# HSens.net
KiCad netlist of a schematic drawn in Altium Designer
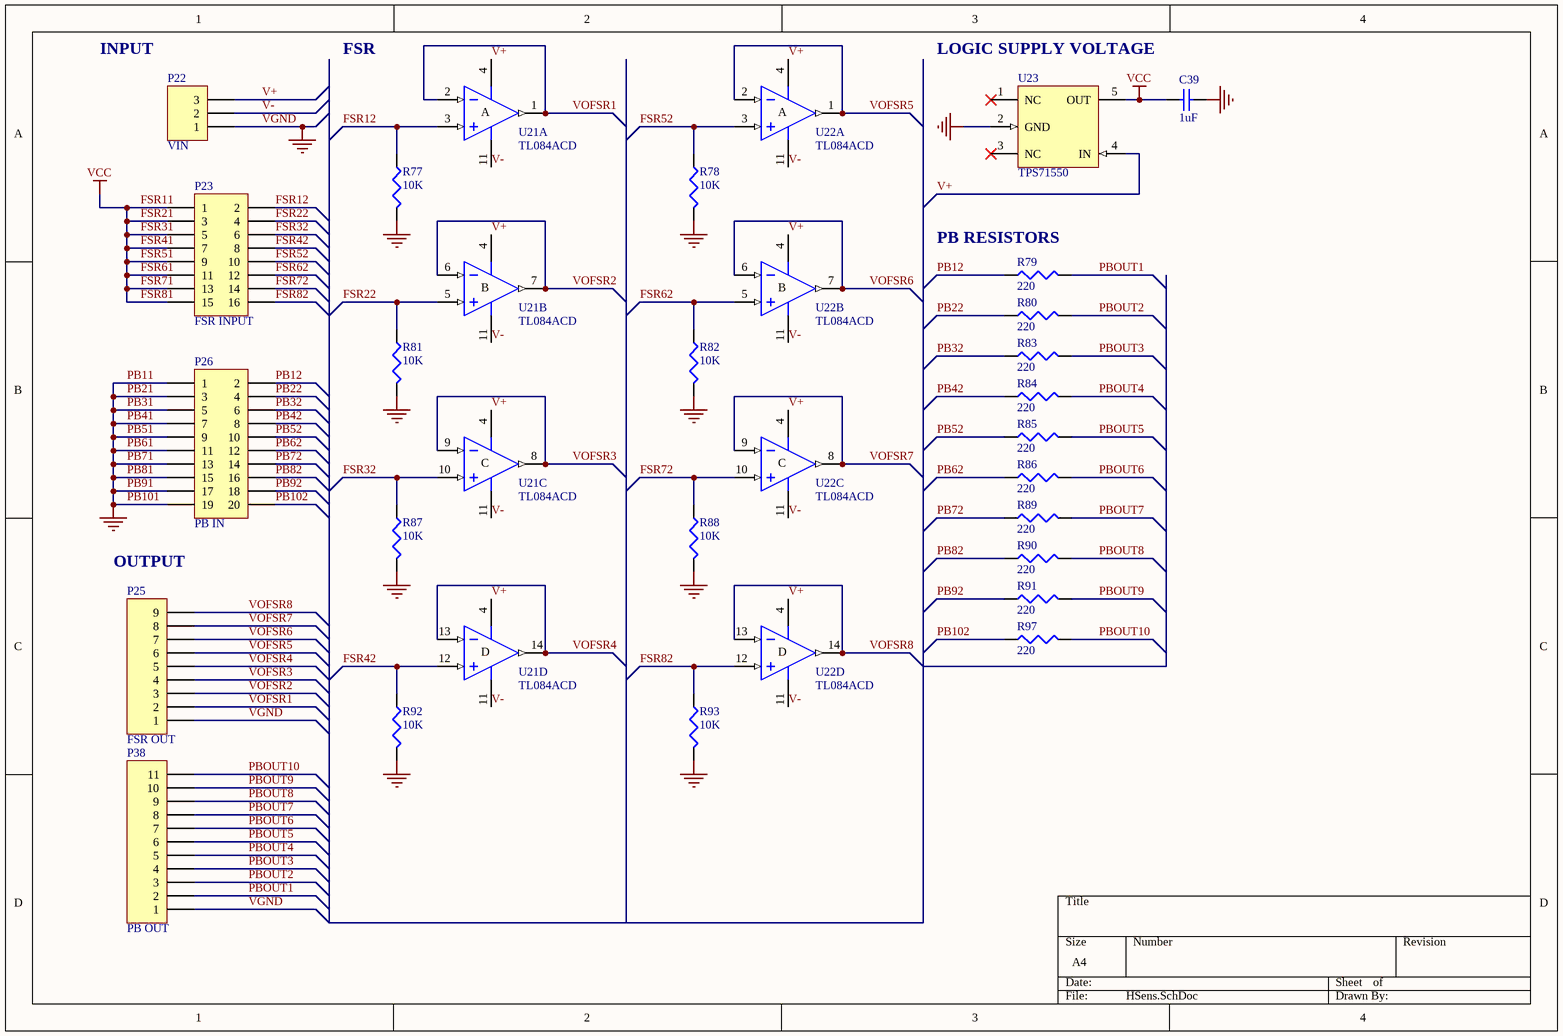
[diagram p0: HSens.SchDoc]

(export (version "E")
  (design (tool "Eeschema 10.0.6"))
  (components
    (comp (ref "C39")
      (value "1uF")
      (footprint "CAPC2012M")
      (description "Capacitor (Semiconductor SIM Model)")
      (fields (field (name "Comment") "Cap Semi") (field (name "PUBLISHER") "Altium Limited"))
      (libsource (lib "Miscellaneous Devices") (part "Cap Semi"))
    )
    (comp (ref "P22")
      (value "VIN")
      (footprint "AZUL5-3")
      (description "Header, 3-Pin")
      (fields (field (name "PUBLISHER") "Altium Limited"))
      (libsource (lib "Miscellaneous Connectors") (part "Header 3"))
    )
    (comp (ref "P23")
      (value "FSR INPUT")
      (footprint "HDR2X8")
      (description "Header, 8-Pin, Dual row")
      (fields (field (name "PUBLISHER") "Altium Limited"))
      (libsource (lib "Miscellaneous Connectors") (part "Header 8X2"))
    )
    (comp (ref "P25")
      (value "FSR OUT")
      (footprint "HDR1X9H")
      (description "Header, 9-Pin, Right Angle")
      (fields (field (name "PUBLISHER") "Altium Limited"))
      (libsource (lib "Miscellaneous Connectors") (part "Header 9H"))
    )
    (comp (ref "P26")
      (value "PB IN")
      (footprint "HDR2X10")
      (description "Header, 10-Pin, Dual row")
      (fields (field (name "PUBLISHER") "Altium Limited"))
      (libsource (lib "Miscellaneous Connectors") (part "Header 10X2"))
    )
    (comp (ref "P38")
      (value "PB OUT")
      (footprint "HDR1X11H")
      (description "Header, 11-Pin, Right Angle")
      (fields (field (name "PUBLISHER") "Altium Limited"))
      (libsource (lib "Miscellaneous Connectors") (part "Header 11H"))
    )
    (comp (ref "R77")
      (value "10K")
      (footprint "RESC3225M")
      (description "Resistor")
      (fields (field (name "Comment") "Res3") (field (name "PUBLISHER") "Altium Limited"))
      (libsource (lib "Miscellaneous Devices") (part "Res3"))
    )
    (comp (ref "R78")
      (value "10K")
      (footprint "RESC3225M")
      (description "Resistor")
      (fields (field (name "Comment") "Res3") (field (name "PUBLISHER") "Altium Limited"))
      (libsource (lib "Miscellaneous Devices") (part "Res3"))
    )
    (comp (ref "R79")
      (value "220")
      (footprint "RESC3225M")
      (description "Resistor")
      (fields (field (name "Comment") "Res3") (field (name "PUBLISHER") "Altium Limited"))
      (libsource (lib "Miscellaneous Devices") (part "Res3"))
    )
    (comp (ref "R80")
      (value "220")
      (footprint "RESC3225M")
      (description "Resistor")
      (fields (field (name "Comment") "Res3") (field (name "PUBLISHER") "Altium Limited"))
      (libsource (lib "Miscellaneous Devices") (part "Res3"))
    )
    (comp (ref "R81")
      (value "10K")
      (footprint "RESC3225M")
      (description "Resistor")
      (fields (field (name "Comment") "Res3") (field (name "PUBLISHER") "Altium Limited"))
      (libsource (lib "Miscellaneous Devices") (part "Res3"))
    )
    (comp (ref "R82")
      (value "10K")
      (footprint "RESC3225M")
      (description "Resistor")
      (fields (field (name "Comment") "Res3") (field (name "PUBLISHER") "Altium Limited"))
      (libsource (lib "Miscellaneous Devices") (part "Res3"))
    )
    (comp (ref "R83")
      (value "220")
      (footprint "RESC3225M")
      (description "Resistor")
      (fields (field (name "Comment") "Res3") (field (name "PUBLISHER") "Altium Limited"))
      (libsource (lib "Miscellaneous Devices") (part "Res3"))
    )
    (comp (ref "R84")
      (value "220")
      (footprint "RESC3225M")
      (description "Resistor")
      (fields (field (name "Comment") "Res3") (field (name "PUBLISHER") "Altium Limited"))
      (libsource (lib "Miscellaneous Devices") (part "Res3"))
    )
    (comp (ref "R85")
      (value "220")
      (footprint "RESC3225M")
      (description "Resistor")
      (fields (field (name "Comment") "Res3") (field (name "PUBLISHER") "Altium Limited"))
      (libsource (lib "Miscellaneous Devices") (part "Res3"))
    )
    (comp (ref "R86")
      (value "220")
      (footprint "RESC3225M")
      (description "Resistor")
      (fields (field (name "Comment") "Res3") (field (name "PUBLISHER") "Altium Limited"))
      (libsource (lib "Miscellaneous Devices") (part "Res3"))
    )
    (comp (ref "R87")
      (value "10K")
      (footprint "RESC3225M")
      (description "Resistor")
      (fields (field (name "Comment") "Res3") (field (name "PUBLISHER") "Altium Limited"))
      (libsource (lib "Miscellaneous Devices") (part "Res3"))
    )
    (comp (ref "R88")
      (value "10K")
      (footprint "RESC3225M")
      (description "Resistor")
      (fields (field (name "Comment") "Res3") (field (name "PUBLISHER") "Altium Limited"))
      (libsource (lib "Miscellaneous Devices") (part "Res3"))
    )
    (comp (ref "R89")
      (value "220")
      (footprint "RESC3225M")
      (description "Resistor")
      (fields (field (name "Comment") "Res3") (field (name "PUBLISHER") "Altium Limited"))
      (libsource (lib "Miscellaneous Devices") (part "Res3"))
    )
    (comp (ref "R90")
      (value "220")
      (footprint "RESC3225M")
      (description "Resistor")
      (fields (field (name "Comment") "Res3") (field (name "PUBLISHER") "Altium Limited"))
      (libsource (lib "Miscellaneous Devices") (part "Res3"))
    )
    (comp (ref "R91")
      (value "220")
      (footprint "RESC3225M")
      (description "Resistor")
      (fields (field (name "Comment") "Res3") (field (name "PUBLISHER") "Altium Limited"))
      (libsource (lib "Miscellaneous Devices") (part "Res3"))
    )
    (comp (ref "R92")
      (value "10K")
      (footprint "RESC3225M")
      (description "Resistor")
      (fields (field (name "Comment") "Res3") (field (name "PUBLISHER") "Altium Limited"))
      (libsource (lib "Miscellaneous Devices") (part "Res3"))
    )
    (comp (ref "R93")
      (value "10K")
      (footprint "RESC3225M")
      (description "Resistor")
      (fields (field (name "Comment") "Res3") (field (name "PUBLISHER") "Altium Limited"))
      (libsource (lib "Miscellaneous Devices") (part "Res3"))
    )
    (comp (ref "R97")
      (value "220")
      (footprint "RESC3225M")
      (description "Resistor")
      (fields (field (name "Comment") "Res3") (field (name "PUBLISHER") "Altium Limited"))
      (libsource (lib "Miscellaneous Devices") (part "Res3"))
    )
    (comp (ref "U21")
      (value "TL084ACD")
      (footprint "SO14_N")
      (description "General-Purpose J-FET Quad Operational Amplifier")
      (fields (field (name "PUBLISHER") "Altium Limited"))
      (libsource (lib "ST Operational Amplifier") (part "TL084ACD"))
    )
    (comp (ref "U22")
      (value "TL084ACD")
      (footprint "SO14_N")
      (description "General-Purpose J-FET Quad Operational Amplifier")
      (fields (field (name "PUBLISHER") "Altium Limited"))
      (libsource (lib "ST Operational Amplifier") (part "TL084ACD"))
    )
    (comp (ref "U23")
      (value "TPS71550")
      (footprint "SOT353-5L")
      (libsource (lib "LitoLibrary") (part "TPS71550"))
    )
  )
  (nets
    (net (code "1") (name "/FSR12") (class "Default")
      (node (ref "P23") (pin "2") (pinfunction "2_2") (pintype "passive"))
      (node (ref "R77") (pin "1") (pinfunction "1_1") (pintype "passive"))
      (node (ref "U21") (pin "3") (pinfunction "IN+_3") (pintype "input"))
    )
    (net (code "2") (name "/FSR22") (class "Default")
      (node (ref "P23") (pin "4") (pinfunction "4_4") (pintype "passive"))
      (node (ref "R81") (pin "1") (pinfunction "1_1") (pintype "passive"))
      (node (ref "U21") (pin "5") (pinfunction "IN+_5") (pintype "input"))
    )
    (net (code "3") (name "/FSR32") (class "Default")
      (node (ref "P23") (pin "6") (pinfunction "6_6") (pintype "passive"))
      (node (ref "R87") (pin "1") (pinfunction "1_1") (pintype "passive"))
      (node (ref "U21") (pin "10") (pinfunction "IN+_10") (pintype "input"))
    )
    (net (code "4") (name "/FSR42") (class "Default")
      (node (ref "P23") (pin "8") (pinfunction "8_8") (pintype "passive"))
      (node (ref "R92") (pin "1") (pinfunction "1_1") (pintype "passive"))
      (node (ref "U21") (pin "12") (pinfunction "IN+_12") (pintype "input"))
    )
    (net (code "5") (name "/FSR52") (class "Default")
      (node (ref "P23") (pin "10") (pinfunction "10_10") (pintype "passive"))
      (node (ref "R78") (pin "1") (pinfunction "1_1") (pintype "passive"))
      (node (ref "U22") (pin "3") (pinfunction "IN+_3") (pintype "input"))
    )
    (net (code "6") (name "/FSR62") (class "Default")
      (node (ref "P23") (pin "12") (pinfunction "12_12") (pintype "passive"))
      (node (ref "R82") (pin "1") (pinfunction "1_1") (pintype "passive"))
      (node (ref "U22") (pin "5") (pinfunction "IN+_5") (pintype "input"))
    )
    (net (code "7") (name "/FSR72") (class "Default")
      (node (ref "P23") (pin "14") (pinfunction "14_14") (pintype "passive"))
      (node (ref "R88") (pin "1") (pinfunction "1_1") (pintype "passive"))
      (node (ref "U22") (pin "10") (pinfunction "IN+_10") (pintype "input"))
    )
    (net (code "8") (name "/FSR82") (class "Default")
      (node (ref "P23") (pin "16") (pinfunction "16_16") (pintype "passive"))
      (node (ref "R93") (pin "1") (pinfunction "1_1") (pintype "passive"))
      (node (ref "U22") (pin "12") (pinfunction "IN+_12") (pintype "input"))
    )
    (net (code "9") (name "/PB12") (class "Default")
      (node (ref "P26") (pin "2") (pinfunction "2_2") (pintype "passive"))
      (node (ref "R79") (pin "1") (pinfunction "1_1") (pintype "passive"))
    )
    (net (code "10") (name "/PB22") (class "Default")
      (node (ref "P26") (pin "4") (pinfunction "4_4") (pintype "passive"))
      (node (ref "R80") (pin "1") (pinfunction "1_1") (pintype "passive"))
    )
    (net (code "11") (name "/PB32") (class "Default")
      (node (ref "P26") (pin "6") (pinfunction "6_6") (pintype "passive"))
      (node (ref "R83") (pin "1") (pinfunction "1_1") (pintype "passive"))
    )
    (net (code "12") (name "/PB42") (class "Default")
      (node (ref "P26") (pin "8") (pinfunction "8_8") (pintype "passive"))
      (node (ref "R84") (pin "1") (pinfunction "1_1") (pintype "passive"))
    )
    (net (code "13") (name "/PB52") (class "Default")
      (node (ref "P26") (pin "10") (pinfunction "10_10") (pintype "passive"))
      (node (ref "R85") (pin "1") (pinfunction "1_1") (pintype "passive"))
    )
    (net (code "14") (name "/PB62") (class "Default")
      (node (ref "P26") (pin "12") (pinfunction "12_12") (pintype "passive"))
      (node (ref "R86") (pin "1") (pinfunction "1_1") (pintype "passive"))
    )
    (net (code "15") (name "/PB72") (class "Default")
      (node (ref "P26") (pin "14") (pinfunction "14_14") (pintype "passive"))
      (node (ref "R89") (pin "1") (pinfunction "1_1") (pintype "passive"))
    )
    (net (code "16") (name "/PB82") (class "Default")
      (node (ref "P26") (pin "16") (pinfunction "16_16") (pintype "passive"))
      (node (ref "R90") (pin "1") (pinfunction "1_1") (pintype "passive"))
    )
    (net (code "17") (name "/PB92") (class "Default")
      (node (ref "P26") (pin "18") (pinfunction "18_18") (pintype "passive"))
      (node (ref "R91") (pin "1") (pinfunction "1_1") (pintype "passive"))
    )
    (net (code "18") (name "/PB102") (class "Default")
      (node (ref "P26") (pin "20") (pinfunction "20_20") (pintype "passive"))
      (node (ref "R97") (pin "1") (pinfunction "1_1") (pintype "passive"))
    )
    (net (code "19") (name "/PBOUT1") (class "Default")
      (node (ref "P38") (pin "2") (pinfunction "2_2") (pintype "passive"))
      (node (ref "R79") (pin "2") (pinfunction "2_2") (pintype "passive"))
    )
    (net (code "20") (name "/PBOUT2") (class "Default")
      (node (ref "P38") (pin "3") (pinfunction "3_3") (pintype "passive"))
      (node (ref "R80") (pin "2") (pinfunction "2_2") (pintype "passive"))
    )
    (net (code "21") (name "/PBOUT3") (class "Default")
      (node (ref "P38") (pin "4") (pinfunction "4_4") (pintype "passive"))
      (node (ref "R83") (pin "2") (pinfunction "2_2") (pintype "passive"))
    )
    (net (code "22") (name "/PBOUT4") (class "Default")
      (node (ref "P38") (pin "5") (pinfunction "5_5") (pintype "passive"))
      (node (ref "R84") (pin "2") (pinfunction "2_2") (pintype "passive"))
    )
    (net (code "23") (name "/PBOUT5") (class "Default")
      (node (ref "P38") (pin "6") (pinfunction "6_6") (pintype "passive"))
      (node (ref "R85") (pin "2") (pinfunction "2_2") (pintype "passive"))
    )
    (net (code "24") (name "/PBOUT6") (class "Default")
      (node (ref "P38") (pin "7") (pinfunction "7_7") (pintype "passive"))
      (node (ref "R86") (pin "2") (pinfunction "2_2") (pintype "passive"))
    )
    (net (code "25") (name "/PBOUT7") (class "Default")
      (node (ref "P38") (pin "8") (pinfunction "8_8") (pintype "passive"))
      (node (ref "R89") (pin "2") (pinfunction "2_2") (pintype "passive"))
    )
    (net (code "26") (name "/PBOUT8") (class "Default")
      (node (ref "P38") (pin "9") (pinfunction "9_9") (pintype "passive"))
      (node (ref "R90") (pin "2") (pinfunction "2_2") (pintype "passive"))
    )
    (net (code "27") (name "/PBOUT9") (class "Default")
      (node (ref "P38") (pin "10") (pinfunction "10_10") (pintype "passive"))
      (node (ref "R91") (pin "2") (pinfunction "2_2") (pintype "passive"))
    )
    (net (code "28") (name "/PBOUT10") (class "Default")
      (node (ref "P38") (pin "11") (pinfunction "11_11") (pintype "passive"))
      (node (ref "R97") (pin "2") (pinfunction "2_2") (pintype "passive"))
    )
    (net (code "29") (name "/V+") (class "Default")
      (node (ref "P22") (pin "3") (pinfunction "3_3") (pintype "passive"))
      (node (ref "U21") (pin "4") (pinfunction "V+_4") (pintype "power_in"))
      (node (ref "U22") (pin "4") (pinfunction "V+_4") (pintype "power_in"))
      (node (ref "U23") (pin "4") (pinfunction "IN_4") (pintype "input"))
    )
    (net (code "30") (name "/V-") (class "Default")
      (node (ref "P22") (pin "2") (pinfunction "2_2") (pintype "passive"))
      (node (ref "U21") (pin "11") (pinfunction "V-_11") (pintype "power_in"))
      (node (ref "U22") (pin "11") (pinfunction "V-_11") (pintype "power_in"))
    )
    (net (code "31") (name "/VOFSR1") (class "Default")
      (node (ref "P25") (pin "2") (pinfunction "2_2") (pintype "passive"))
      (node (ref "U21") (pin "1") (pinfunction "OUT_1") (pintype "output"))
      (node (ref "U21") (pin "2") (pinfunction "IN-_2") (pintype "input"))
    )
    (net (code "32") (name "/VOFSR2") (class "Default")
      (node (ref "P25") (pin "3") (pinfunction "3_3") (pintype "passive"))
      (node (ref "U21") (pin "6") (pinfunction "IN-_6") (pintype "input"))
      (node (ref "U21") (pin "7") (pinfunction "OUT_7") (pintype "output"))
    )
    (net (code "33") (name "/VOFSR3") (class "Default")
      (node (ref "P25") (pin "4") (pinfunction "4_4") (pintype "passive"))
      (node (ref "U21") (pin "8") (pinfunction "OUT_8") (pintype "output"))
      (node (ref "U21") (pin "9") (pinfunction "IN-_9") (pintype "input"))
    )
    (net (code "34") (name "/VOFSR4") (class "Default")
      (node (ref "P25") (pin "5") (pinfunction "5_5") (pintype "passive"))
      (node (ref "U21") (pin "13") (pinfunction "IN-_13") (pintype "input"))
      (node (ref "U21") (pin "14") (pinfunction "OUT_14") (pintype "output"))
    )
    (net (code "35") (name "/VOFSR5") (class "Default")
      (node (ref "P25") (pin "6") (pinfunction "6_6") (pintype "passive"))
      (node (ref "U22") (pin "1") (pinfunction "OUT_1") (pintype "output"))
      (node (ref "U22") (pin "2") (pinfunction "IN-_2") (pintype "input"))
    )
    (net (code "36") (name "/VOFSR6") (class "Default")
      (node (ref "P25") (pin "7") (pinfunction "7_7") (pintype "passive"))
      (node (ref "U22") (pin "6") (pinfunction "IN-_6") (pintype "input"))
      (node (ref "U22") (pin "7") (pinfunction "OUT_7") (pintype "output"))
    )
    (net (code "37") (name "/VOFSR7") (class "Default")
      (node (ref "P25") (pin "8") (pinfunction "8_8") (pintype "passive"))
      (node (ref "U22") (pin "8") (pinfunction "OUT_8") (pintype "output"))
      (node (ref "U22") (pin "9") (pinfunction "IN-_9") (pintype "input"))
    )
    (net (code "38") (name "/VOFSR8") (class "Default")
      (node (ref "P25") (pin "9") (pinfunction "9_9") (pintype "passive"))
      (node (ref "U22") (pin "13") (pinfunction "IN-_13") (pintype "input"))
      (node (ref "U22") (pin "14") (pinfunction "OUT_14") (pintype "output"))
    )
    (net (code "39") (name "GND") (class "Default")
      (node (ref "C39") (pin "2") (pinfunction "2_2") (pintype "passive"))
      (node (ref "P22") (pin "1") (pinfunction "1_1") (pintype "passive"))
      (node (ref "P25") (pin "1") (pinfunction "1_1") (pintype "passive"))
      (node (ref "P26") (pin "1") (pinfunction "1_1") (pintype "passive"))
      (node (ref "P26") (pin "11") (pinfunction "11_11") (pintype "passive"))
      (node (ref "P26") (pin "13") (pinfunction "13_13") (pintype "passive"))
      (node (ref "P26") (pin "15") (pinfunction "15_15") (pintype "passive"))
      (node (ref "P26") (pin "17") (pinfunction "17_17") (pintype "passive"))
      (node (ref "P26") (pin "19") (pinfunction "19_19") (pintype "passive"))
      (node (ref "P26") (pin "3") (pinfunction "3_3") (pintype "passive"))
      (node (ref "P26") (pin "5") (pinfunction "5_5") (pintype "passive"))
      (node (ref "P26") (pin "7") (pinfunction "7_7") (pintype "passive"))
      (node (ref "P26") (pin "9") (pinfunction "9_9") (pintype "passive"))
      (node (ref "P38") (pin "1") (pinfunction "1_1") (pintype "passive"))
      (node (ref "R77") (pin "2") (pinfunction "2_2") (pintype "passive"))
      (node (ref "R78") (pin "2") (pinfunction "2_2") (pintype "passive"))
      (node (ref "R81") (pin "2") (pinfunction "2_2") (pintype "passive"))
      (node (ref "R82") (pin "2") (pinfunction "2_2") (pintype "passive"))
      (node (ref "R87") (pin "2") (pinfunction "2_2") (pintype "passive"))
      (node (ref "R88") (pin "2") (pinfunction "2_2") (pintype "passive"))
      (node (ref "R92") (pin "2") (pinfunction "2_2") (pintype "passive"))
      (node (ref "R93") (pin "2") (pinfunction "2_2") (pintype "passive"))
      (node (ref "U23") (pin "2") (pinfunction "GND_2") (pintype "input"))
    )
    (net (code "40") (name "VCC") (class "Default")
      (node (ref "C39") (pin "1") (pinfunction "1_1") (pintype "passive"))
      (node (ref "P23") (pin "1") (pinfunction "1_1") (pintype "passive"))
      (node (ref "P23") (pin "11") (pinfunction "11_11") (pintype "passive"))
      (node (ref "P23") (pin "13") (pinfunction "13_13") (pintype "passive"))
      (node (ref "P23") (pin "15") (pinfunction "15_15") (pintype "passive"))
      (node (ref "P23") (pin "3") (pinfunction "3_3") (pintype "passive"))
      (node (ref "P23") (pin "5") (pinfunction "5_5") (pintype "passive"))
      (node (ref "P23") (pin "7") (pinfunction "7_7") (pintype "passive"))
      (node (ref "P23") (pin "9") (pinfunction "9_9") (pintype "passive"))
      (node (ref "U23") (pin "5") (pinfunction "OUT_5") (pintype "passive"))
    )
    (net (code "41") (name "unconnected-(U23-NC-Pad1)") (class "Default")
      (node (ref "U23") (pin "1") (pinfunction "NC_1") (pintype "passive+no_connect"))
    )
    (net (code "42") (name "unconnected-(U23-NC-Pad3)") (class "Default")
      (node (ref "U23") (pin "3") (pinfunction "NC_3") (pintype "passive+no_connect"))
    )
  )
)
